# G1000_Buttons_Right.net
KiCad netlist of a schematic drawn in EasyEDA
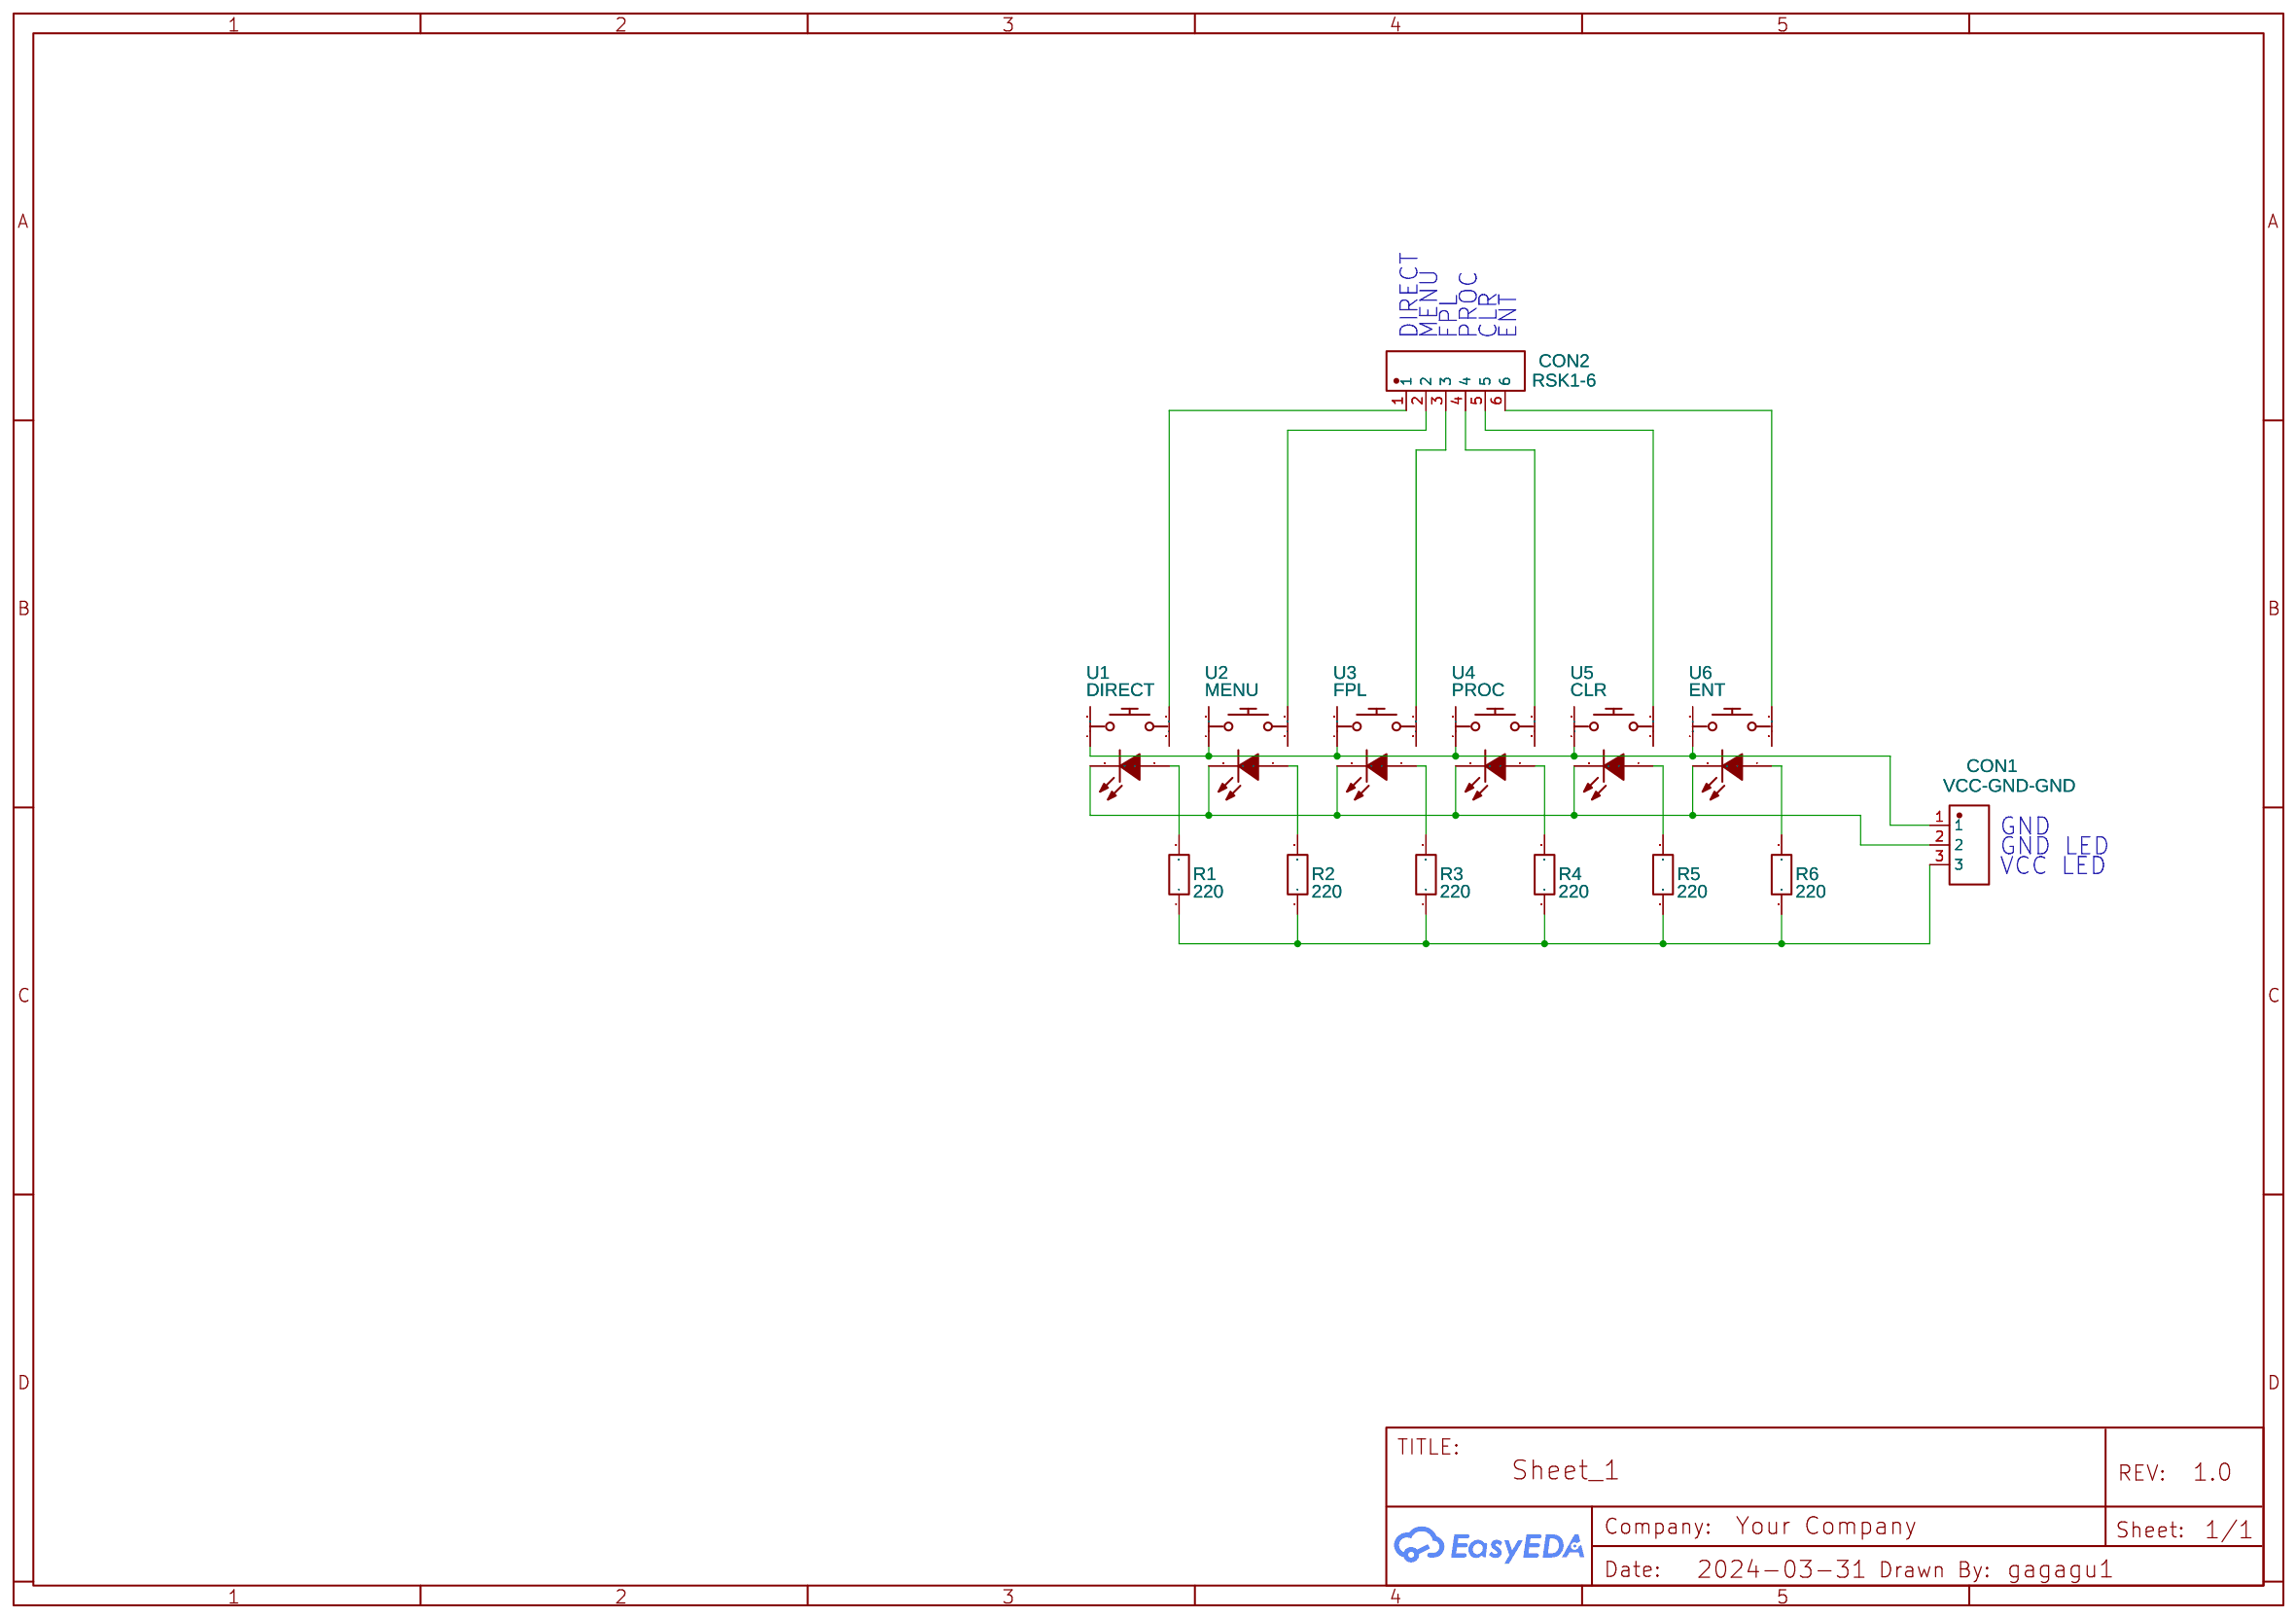
[diagram p0: schematic sheet]

(export (version "E")
  (design (tool "Eeschema 10.0.6"))
  (components
    (comp (ref "CON1")
      (value "VCC-GND-GND")
      (fields (field (name "Manufacturer Part") "HC-XH-3A-G") (field (name "Manufacturer") "HCTL(华灿天禄)"))
      (libsource (lib "") (part "HC-XH-3A-G"))
    )
    (comp (ref "CON2")
      (value "RSK1-6")
      (fields (field (name "Manufacturer Part") "XH-6A") (field (name "Manufacturer") "CAX"))
      (libsource (lib "") (part "ARUN-CONN-TH_XH-6A"))
    )
    (comp (ref "R1") (value "220") (libsource (lib "") (part "R_AXIAL-0.4_EU")))
    (comp (ref "R2") (value "220") (libsource (lib "") (part "R_AXIAL-0.4_EU")))
    (comp (ref "R3") (value "220") (libsource (lib "") (part "R_AXIAL-0.4_EU")))
    (comp (ref "R4") (value "220") (libsource (lib "") (part "R_AXIAL-0.4_EU")))
    (comp (ref "R5") (value "220") (libsource (lib "") (part "R_AXIAL-0.4_EU")))
    (comp (ref "R6") (value "220") (libsource (lib "") (part "R_AXIAL-0.4_EU")))
    (comp (ref "U1") (value "DIRECT") (libsource (lib "") (part "6X6_LED+PUSHBUTTON V2")))
    (comp (ref "U2") (value "MENU") (libsource (lib "") (part "6X6_LED+PUSHBUTTON V2")))
    (comp (ref "U3") (value "FPL") (libsource (lib "") (part "6X6_LED+PUSHBUTTON V2")))
    (comp (ref "U4") (value "PROC") (libsource (lib "") (part "6X6_LED+PUSHBUTTON V2")))
    (comp (ref "U5") (value "CLR") (libsource (lib "") (part "6X6_LED+PUSHBUTTON V2")))
    (comp (ref "U6") (value "ENT") (libsource (lib "") (part "6X6_LED+PUSHBUTTON V2")))
  )
  (nets
    (net (code "1") (name "Net-(CON1-Pad1)") (class "Default")
      (node (ref "CON1") (pin "1") (pinfunction "1_1") (pintype "unspecified"))
      (node (ref "U1") (pin "4") (pinfunction "4_4") (pintype "unspecified"))
      (node (ref "U2") (pin "4") (pinfunction "4_4") (pintype "unspecified"))
      (node (ref "U3") (pin "4") (pinfunction "4_4") (pintype "unspecified"))
      (node (ref "U4") (pin "4") (pinfunction "4_4") (pintype "unspecified"))
      (node (ref "U5") (pin "4") (pinfunction "4_4") (pintype "unspecified"))
      (node (ref "U6") (pin "4") (pinfunction "4_4") (pintype "unspecified"))
    )
    (net (code "2") (name "Net-(CON1-Pad2)") (class "Default")
      (node (ref "CON1") (pin "2") (pinfunction "2_2") (pintype "unspecified"))
      (node (ref "U1") (pin "C") (pinfunction "C_C") (pintype "unspecified"))
      (node (ref "U2") (pin "C") (pinfunction "C_C") (pintype "unspecified"))
      (node (ref "U3") (pin "C") (pinfunction "C_C") (pintype "unspecified"))
      (node (ref "U4") (pin "C") (pinfunction "C_C") (pintype "unspecified"))
      (node (ref "U5") (pin "C") (pinfunction "C_C") (pintype "unspecified"))
      (node (ref "U6") (pin "C") (pinfunction "C_C") (pintype "unspecified"))
    )
    (net (code "3") (name "Net-(CON1-Pad3)") (class "Default")
      (node (ref "CON1") (pin "3") (pinfunction "3_3") (pintype "unspecified"))
      (node (ref "R1") (pin "1") (pinfunction "1_1") (pintype "unspecified"))
      (node (ref "R2") (pin "1") (pinfunction "1_1") (pintype "unspecified"))
      (node (ref "R3") (pin "1") (pinfunction "1_1") (pintype "unspecified"))
      (node (ref "R4") (pin "1") (pinfunction "1_1") (pintype "unspecified"))
      (node (ref "R5") (pin "1") (pinfunction "1_1") (pintype "unspecified"))
      (node (ref "R6") (pin "1") (pinfunction "1_1") (pintype "unspecified"))
    )
    (net (code "4") (name "Net-(CON2-Pad1)") (class "Default")
      (node (ref "CON2") (pin "1") (pinfunction "1_1") (pintype "unspecified"))
      (node (ref "U1") (pin "1") (pinfunction "1_1") (pintype "unspecified"))
    )
    (net (code "5") (name "Net-(CON2-Pad2)") (class "Default")
      (node (ref "CON2") (pin "2") (pinfunction "2_2") (pintype "unspecified"))
      (node (ref "U2") (pin "1") (pinfunction "1_1") (pintype "unspecified"))
    )
    (net (code "6") (name "Net-(CON2-Pad3)") (class "Default")
      (node (ref "CON2") (pin "3") (pinfunction "3_3") (pintype "unspecified"))
      (node (ref "U3") (pin "1") (pinfunction "1_1") (pintype "unspecified"))
    )
    (net (code "7") (name "Net-(CON2-Pad4)") (class "Default")
      (node (ref "CON2") (pin "4") (pinfunction "4_4") (pintype "unspecified"))
      (node (ref "U4") (pin "1") (pinfunction "1_1") (pintype "unspecified"))
    )
    (net (code "8") (name "Net-(CON2-Pad5)") (class "Default")
      (node (ref "CON2") (pin "5") (pinfunction "5_5") (pintype "unspecified"))
      (node (ref "U5") (pin "1") (pinfunction "1_1") (pintype "unspecified"))
    )
    (net (code "9") (name "Net-(CON2-Pad6)") (class "Default")
      (node (ref "CON2") (pin "6") (pinfunction "6_6") (pintype "unspecified"))
      (node (ref "U6") (pin "1") (pinfunction "1_1") (pintype "unspecified"))
    )
    (net (code "10") (name "Net-(R1-Pad2)") (class "Default")
      (node (ref "R1") (pin "2") (pinfunction "2_2") (pintype "unspecified"))
      (node (ref "U1") (pin "A") (pinfunction "A_A") (pintype "unspecified"))
    )
    (net (code "11") (name "Net-(R2-Pad2)") (class "Default")
      (node (ref "R2") (pin "2") (pinfunction "2_2") (pintype "unspecified"))
      (node (ref "U2") (pin "A") (pinfunction "A_A") (pintype "unspecified"))
    )
    (net (code "12") (name "Net-(R3-Pad2)") (class "Default")
      (node (ref "R3") (pin "2") (pinfunction "2_2") (pintype "unspecified"))
      (node (ref "U3") (pin "A") (pinfunction "A_A") (pintype "unspecified"))
    )
    (net (code "13") (name "Net-(R4-Pad2)") (class "Default")
      (node (ref "R4") (pin "2") (pinfunction "2_2") (pintype "unspecified"))
      (node (ref "U4") (pin "A") (pinfunction "A_A") (pintype "unspecified"))
    )
    (net (code "14") (name "Net-(R5-Pad2)") (class "Default")
      (node (ref "R5") (pin "2") (pinfunction "2_2") (pintype "unspecified"))
      (node (ref "U5") (pin "A") (pinfunction "A_A") (pintype "unspecified"))
    )
    (net (code "15") (name "Net-(R6-Pad2)") (class "Default")
      (node (ref "R6") (pin "2") (pinfunction "2_2") (pintype "unspecified"))
      (node (ref "U6") (pin "A") (pinfunction "A_A") (pintype "unspecified"))
    )
    (net (code "16") (name "unconnected-(U1-Pad2)") (class "Default")
      (node (ref "U1") (pin "2") (pinfunction "2_2") (pintype "unspecified"))
    )
    (net (code "17") (name "unconnected-(U1-Pad3)") (class "Default")
      (node (ref "U1") (pin "3") (pinfunction "3_3") (pintype "unspecified"))
    )
    (net (code "18") (name "unconnected-(U2-Pad2)") (class "Default")
      (node (ref "U2") (pin "2") (pinfunction "2_2") (pintype "unspecified"))
    )
    (net (code "19") (name "unconnected-(U2-Pad3)") (class "Default")
      (node (ref "U2") (pin "3") (pinfunction "3_3") (pintype "unspecified"))
    )
    (net (code "20") (name "unconnected-(U3-Pad2)") (class "Default")
      (node (ref "U3") (pin "2") (pinfunction "2_2") (pintype "unspecified"))
    )
    (net (code "21") (name "unconnected-(U3-Pad3)") (class "Default")
      (node (ref "U3") (pin "3") (pinfunction "3_3") (pintype "unspecified"))
    )
    (net (code "22") (name "unconnected-(U4-Pad2)") (class "Default")
      (node (ref "U4") (pin "2") (pinfunction "2_2") (pintype "unspecified"))
    )
    (net (code "23") (name "unconnected-(U4-Pad3)") (class "Default")
      (node (ref "U4") (pin "3") (pinfunction "3_3") (pintype "unspecified"))
    )
    (net (code "24") (name "unconnected-(U5-Pad2)") (class "Default")
      (node (ref "U5") (pin "2") (pinfunction "2_2") (pintype "unspecified"))
    )
    (net (code "25") (name "unconnected-(U5-Pad3)") (class "Default")
      (node (ref "U5") (pin "3") (pinfunction "3_3") (pintype "unspecified"))
    )
    (net (code "26") (name "unconnected-(U6-Pad2)") (class "Default")
      (node (ref "U6") (pin "2") (pinfunction "2_2") (pintype "unspecified"))
    )
    (net (code "27") (name "unconnected-(U6-Pad3)") (class "Default")
      (node (ref "U6") (pin "3") (pinfunction "3_3") (pintype "unspecified"))
    )
  )
)
